# SCH_Display-Button_EasyEDA.net
KiCad netlist of a schematic drawn in EasyEDA
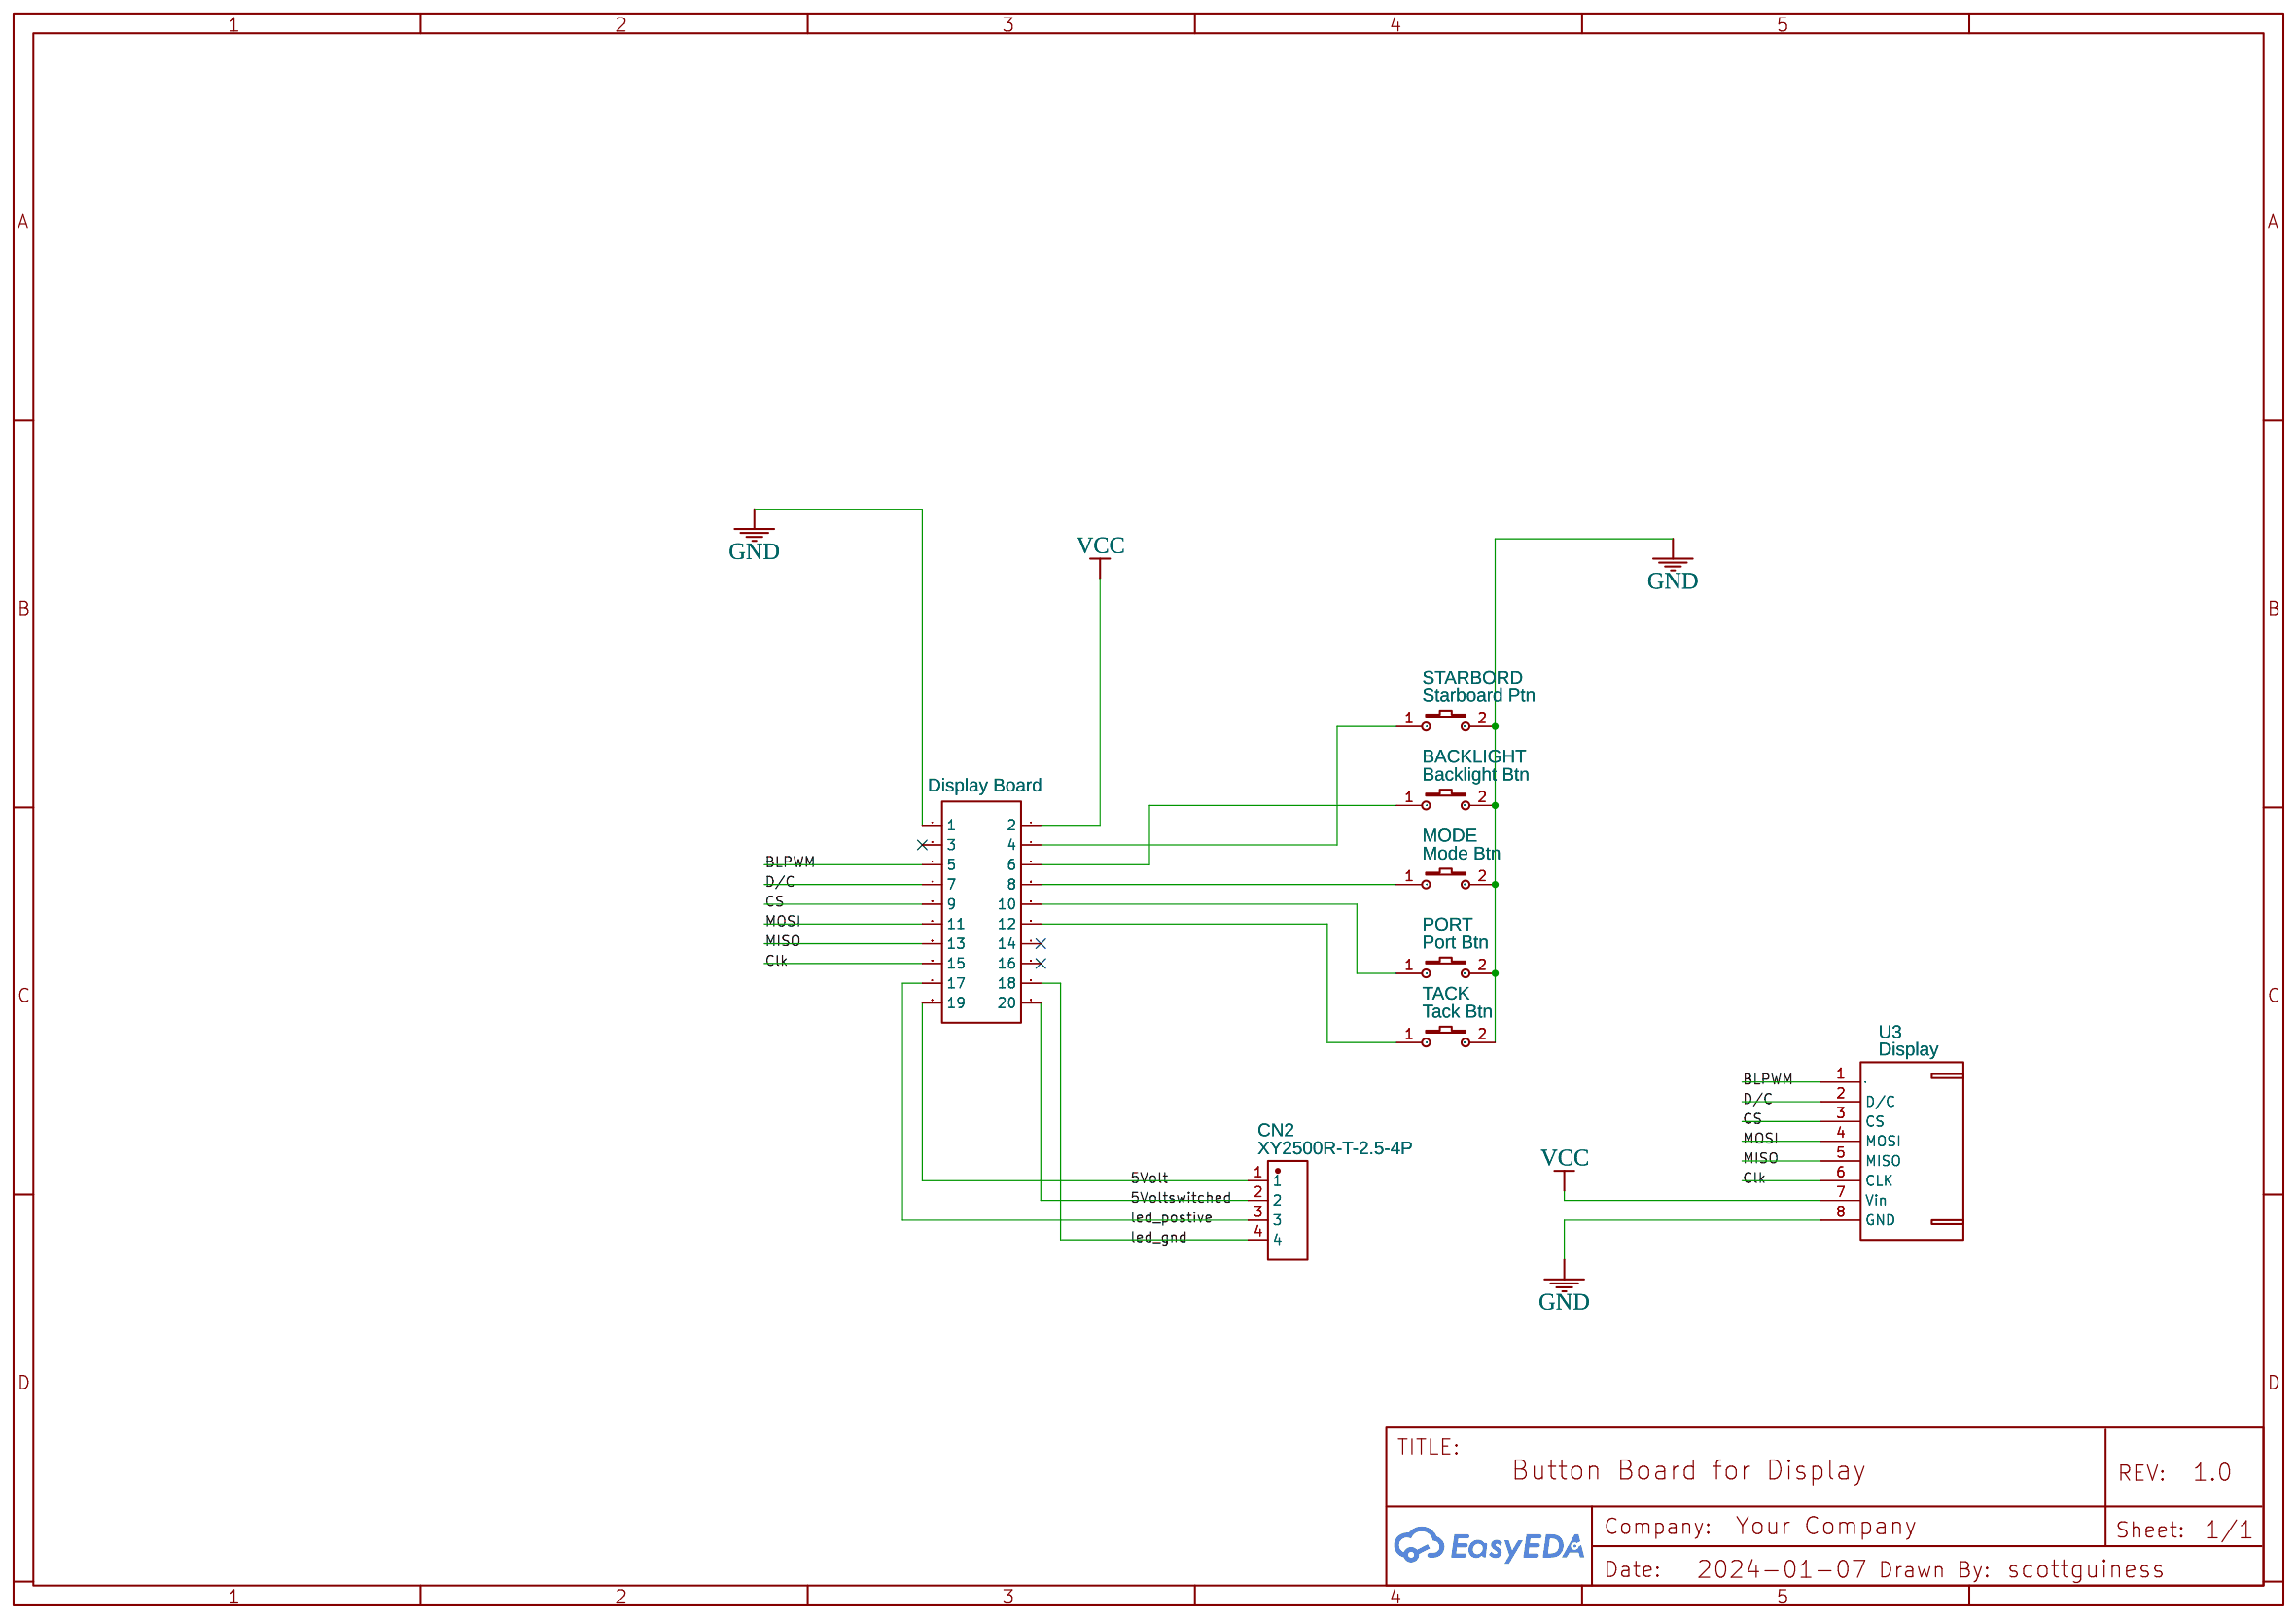
[diagram p0: schematic sheet]

(export (version "E")
  (design (tool "Eeschema 10.0.6"))
  (components
    (comp (ref "BACKLIGHT")
      (value "Backlight Btn")
      (fields (field (name "Manufacturer Part") "K2-1107ST-A4SW-06"))
      (libsource (lib "") (part "K2-3.6×6.1_SMD_1"))
    )
    (comp (ref "BUTTON_LED1") (value "Display Board") (libsource (lib "") (part "HDR-M-2.54_2x10")))
    (comp (ref "CN2")
      (value "XY2500R-T-2.5-4P")
      (fields (field (name "Manufacturer") "XINLAIYA(新莱亚)"))
      (libsource (lib "") (part "XY2500R-T-2.5-4P"))
    )
    (comp (ref "MODE")
      (value "Mode Btn")
      (fields (field (name "Manufacturer Part") "K2-1107ST-A4SW-06"))
      (libsource (lib "") (part "K2-3.6×6.1_SMD_2"))
    )
    (comp (ref "PORT")
      (value "Port Btn")
      (fields (field (name "Manufacturer Part") "K2-1107ST-A4SW-06"))
      (libsource (lib "") (part "K2-3.6×6.1_SMD"))
    )
    (comp (ref "STARBORD")
      (value "Starboard Ptn")
      (fields (field (name "Manufacturer Part") "K2-1107ST-A4SW-06"))
      (libsource (lib "") (part "K2-3.6×6.1_SMD_3"))
    )
    (comp (ref "TACK")
      (value "Tack Btn")
      (fields (field (name "Manufacturer Part") "K2-1107ST-A4SW-06"))
      (libsource (lib "") (part "K2-3.6×6.1_SMD_4"))
    )
    (comp (ref "U3") (value "Display") (libsource (lib "") (part "JST-XH-8-Pin")))
  )
  (nets
    (net (code "1") (name "/5Volt") (class "Default")
      (node (ref "BUTTON_LED1") (pin "19") (pinfunction "19_19") (pintype "unspecified"))
      (node (ref "CN2") (pin "1") (pinfunction "1_1") (pintype "unspecified"))
    )
    (net (code "2") (name "/5Voltswitched") (class "Default")
      (node (ref "BUTTON_LED1") (pin "20") (pinfunction "20_20") (pintype "unspecified"))
      (node (ref "CN2") (pin "2") (pinfunction "2_2") (pintype "unspecified"))
    )
    (net (code "3") (name "/BLPWM") (class "Default")
      (node (ref "BUTTON_LED1") (pin "5") (pinfunction "5_5") (pintype "unspecified"))
      (node (ref "U3") (pin "1") (pinfunction "1_1") (pintype "unspecified"))
    )
    (net (code "4") (name "/CS") (class "Default")
      (node (ref "BUTTON_LED1") (pin "9") (pinfunction "9_9") (pintype "unspecified"))
      (node (ref "U3") (pin "3") (pinfunction "CS_3") (pintype "unspecified"))
    )
    (net (code "5") (name "/Clk") (class "Default")
      (node (ref "BUTTON_LED1") (pin "15") (pinfunction "15_15") (pintype "unspecified"))
      (node (ref "U3") (pin "6") (pinfunction "CLK_6") (pintype "unspecified"))
    )
    (net (code "6") (name "/D{slash}C") (class "Default")
      (node (ref "BUTTON_LED1") (pin "7") (pinfunction "7_7") (pintype "unspecified"))
      (node (ref "U3") (pin "2") (pinfunction "D/C_2") (pintype "unspecified"))
    )
    (net (code "7") (name "/MISO") (class "Default")
      (node (ref "BUTTON_LED1") (pin "13") (pinfunction "13_13") (pintype "unspecified"))
      (node (ref "U3") (pin "5") (pinfunction "MISO_5") (pintype "unspecified"))
    )
    (net (code "8") (name "/MOSI") (class "Default")
      (node (ref "BUTTON_LED1") (pin "11") (pinfunction "11_11") (pintype "unspecified"))
      (node (ref "U3") (pin "4") (pinfunction "MOSI_4") (pintype "unspecified"))
    )
    (net (code "9") (name "/led_gnd") (class "Default")
      (node (ref "BUTTON_LED1") (pin "18") (pinfunction "18_18") (pintype "unspecified"))
      (node (ref "CN2") (pin "4") (pinfunction "4_4") (pintype "unspecified"))
    )
    (net (code "10") (name "/led_postive") (class "Default")
      (node (ref "BUTTON_LED1") (pin "17") (pinfunction "17_17") (pintype "unspecified"))
      (node (ref "CN2") (pin "3") (pinfunction "3_3") (pintype "unspecified"))
    )
    (net (code "11") (name "GND") (class "Default")
      (node (ref "BACKLIGHT") (pin "2") (pinfunction "2_2") (pintype "unspecified"))
      (node (ref "BUTTON_LED1") (pin "1") (pinfunction "1_1") (pintype "unspecified"))
      (node (ref "MODE") (pin "2") (pinfunction "2_2") (pintype "unspecified"))
      (node (ref "PORT") (pin "2") (pinfunction "2_2") (pintype "unspecified"))
      (node (ref "STARBORD") (pin "2") (pinfunction "2_2") (pintype "unspecified"))
      (node (ref "TACK") (pin "2") (pinfunction "2_2") (pintype "unspecified"))
      (node (ref "U3") (pin "8") (pinfunction "GND_8") (pintype "unspecified"))
    )
    (net (code "12") (name "Net-(BACKLIGHT-Pad1)") (class "Default")
      (node (ref "BACKLIGHT") (pin "1") (pinfunction "1_1") (pintype "unspecified"))
      (node (ref "BUTTON_LED1") (pin "6") (pinfunction "6_6") (pintype "unspecified"))
    )
    (net (code "13") (name "Net-(BUTTON_LED1-Pad4)") (class "Default")
      (node (ref "BUTTON_LED1") (pin "4") (pinfunction "4_4") (pintype "unspecified"))
      (node (ref "STARBORD") (pin "1") (pinfunction "1_1") (pintype "unspecified"))
    )
    (net (code "14") (name "Net-(BUTTON_LED1-Pad8)") (class "Default")
      (node (ref "BUTTON_LED1") (pin "8") (pinfunction "8_8") (pintype "unspecified"))
      (node (ref "MODE") (pin "1") (pinfunction "1_1") (pintype "unspecified"))
    )
    (net (code "15") (name "Net-(BUTTON_LED1-Pad10)") (class "Default")
      (node (ref "BUTTON_LED1") (pin "10") (pinfunction "10_10") (pintype "unspecified"))
      (node (ref "PORT") (pin "1") (pinfunction "1_1") (pintype "unspecified"))
    )
    (net (code "16") (name "Net-(BUTTON_LED1-Pad12)") (class "Default")
      (node (ref "BUTTON_LED1") (pin "12") (pinfunction "12_12") (pintype "unspecified"))
      (node (ref "TACK") (pin "1") (pinfunction "1_1") (pintype "unspecified"))
    )
    (net (code "17") (name "VCC") (class "Default")
      (node (ref "BUTTON_LED1") (pin "2") (pinfunction "2_2") (pintype "unspecified"))
      (node (ref "U3") (pin "7") (pinfunction "Vin_7") (pintype "unspecified"))
    )
    (net (code "18") (name "unconnected-(BUTTON_LED1-Pad3)") (class "Default")
      (node (ref "BUTTON_LED1") (pin "3") (pinfunction "3_3") (pintype "unspecified+no_connect"))
    )
    (net (code "19") (name "unconnected-(BUTTON_LED1-Pad14)") (class "Default")
      (node (ref "BUTTON_LED1") (pin "14") (pinfunction "14_14") (pintype "unspecified+no_connect"))
    )
    (net (code "20") (name "unconnected-(BUTTON_LED1-Pad16)") (class "Default")
      (node (ref "BUTTON_LED1") (pin "16") (pinfunction "16_16") (pintype "unspecified+no_connect"))
    )
  )
)
